# ESP32.net
KiCad netlist of a schematic drawn in Altium Designer
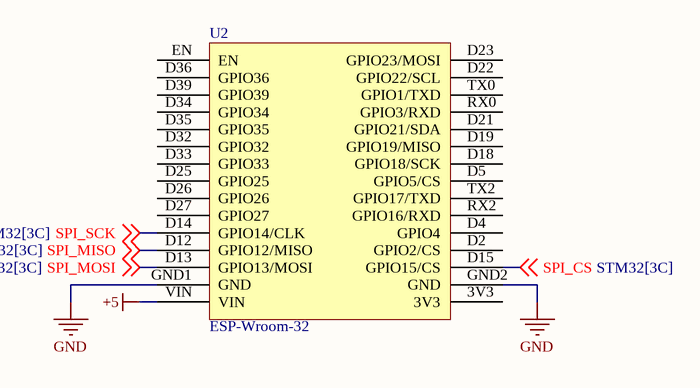
[diagram p0: ESP32.SchDoc]

(export (version "E")
  (design (tool "Eeschema 10.0.6"))
  (components
    (comp (ref "U2")
      (value "ESP-Wroom-32")
      (footprint "MODULE_ESP32_DEVKIT_V1")
      (description "https://lastminuteengineers.com/esp32-pinout-reference/")
      (libsource (lib "MindControlledCarPCB") (part "ESP-Wroom-32"))
    )
  )
  (nets
    (net (code "1") (name "+5") (class "Default")
      (node (ref "U2") (pin "VIN") (pinfunction "VIN_VIN") (pintype "passive"))
    )
    (net (code "2") (name "GND") (class "Default")
      (node (ref "U2") (pin "GND1") (pinfunction "GND_GND1") (pintype "passive"))
      (node (ref "U2") (pin "GND2") (pinfunction "GND_GND2") (pintype "passive"))
    )
    (net (code "3") (name "SPI_CS") (class "Default")
      (node (ref "U2") (pin "D15") (pinfunction "GPIO15/CS_D15") (pintype "passive"))
    )
    (net (code "4") (name "SPI_MISO") (class "Default")
      (node (ref "U2") (pin "D12") (pinfunction "GPIO12/MISO_D12") (pintype "passive"))
    )
    (net (code "5") (name "SPI_MOSI") (class "Default")
      (node (ref "U2") (pin "D13") (pinfunction "GPIO13/MOSI_D13") (pintype "passive"))
    )
    (net (code "6") (name "SPI_SCK") (class "Default")
      (node (ref "U2") (pin "D14") (pinfunction "GPIO14/CLK_D14") (pintype "passive"))
    )
    (net (code "7") (name "unconnected-(U2-GPIO1{slash}TXD-PadTX0)") (class "Default")
      (node (ref "U2") (pin "TX0") (pinfunction "GPIO1/TXD_TX0") (pintype "passive"))
    )
    (net (code "8") (name "unconnected-(U2-GPIO2{slash}CS-PadD2)") (class "Default")
      (node (ref "U2") (pin "D2") (pinfunction "GPIO2/CS_D2") (pintype "passive"))
    )
    (net (code "9") (name "unconnected-(U2-GPIO3{slash}RXD-PadRX0)") (class "Default")
      (node (ref "U2") (pin "RX0") (pinfunction "GPIO3/RXD_RX0") (pintype "passive"))
    )
    (net (code "10") (name "unconnected-(U2-GPIO4-PadD4)") (class "Default")
      (node (ref "U2") (pin "D4") (pinfunction "GPIO4_D4") (pintype "passive"))
    )
    (net (code "11") (name "unconnected-(U2-GPIO5{slash}CS-PadD5)") (class "Default")
      (node (ref "U2") (pin "D5") (pinfunction "GPIO5/CS_D5") (pintype "passive"))
    )
    (net (code "12") (name "unconnected-(U2-GPIO16{slash}RXD-PadRX2)") (class "Default")
      (node (ref "U2") (pin "RX2") (pinfunction "GPIO16/RXD_RX2") (pintype "passive"))
    )
    (net (code "13") (name "unconnected-(U2-GPIO17{slash}TXD-PadTX2)") (class "Default")
      (node (ref "U2") (pin "TX2") (pinfunction "GPIO17/TXD_TX2") (pintype "passive"))
    )
    (net (code "14") (name "unconnected-(U2-GPIO18{slash}SCK-PadD18)") (class "Default")
      (node (ref "U2") (pin "D18") (pinfunction "GPIO18/SCK_D18") (pintype "passive"))
    )
    (net (code "15") (name "unconnected-(U2-GPIO19{slash}MISO-PadD19)") (class "Default")
      (node (ref "U2") (pin "D19") (pinfunction "GPIO19/MISO_D19") (pintype "passive"))
    )
    (net (code "16") (name "unconnected-(U2-GPIO21{slash}SDA-PadD21)") (class "Default")
      (node (ref "U2") (pin "D21") (pinfunction "GPIO21/SDA_D21") (pintype "passive"))
    )
    (net (code "17") (name "unconnected-(U2-GPIO22{slash}SCL-PadD22)") (class "Default")
      (node (ref "U2") (pin "D22") (pinfunction "GPIO22/SCL_D22") (pintype "passive"))
    )
    (net (code "18") (name "unconnected-(U2-GPIO23{slash}MOSI-PadD23)") (class "Default")
      (node (ref "U2") (pin "D23") (pinfunction "GPIO23/MOSI_D23") (pintype "passive"))
    )
    (net (code "19") (name "unconnected-(U2-GPIO25-PadD25)") (class "Default")
      (node (ref "U2") (pin "D25") (pinfunction "GPIO25_D25") (pintype "passive"))
    )
    (net (code "20") (name "unconnected-(U2-GPIO26-PadD26)") (class "Default")
      (node (ref "U2") (pin "D26") (pinfunction "GPIO26_D26") (pintype "passive"))
    )
    (net (code "21") (name "unconnected-(U2-GPIO27-PadD27)") (class "Default")
      (node (ref "U2") (pin "D27") (pinfunction "GPIO27_D27") (pintype "passive"))
    )
    (net (code "22") (name "unconnected-(U2-GPIO32-PadD32)") (class "Default")
      (node (ref "U2") (pin "D32") (pinfunction "GPIO32_D32") (pintype "passive"))
    )
    (net (code "23") (name "unconnected-(U2-GPIO33-PadD33)") (class "Default")
      (node (ref "U2") (pin "D33") (pinfunction "GPIO33_D33") (pintype "passive"))
    )
    (net (code "24") (name "unconnected-(U2-GPIO34-PadD34)") (class "Default")
      (node (ref "U2") (pin "D34") (pinfunction "GPIO34_D34") (pintype "passive"))
    )
    (net (code "25") (name "unconnected-(U2-GPIO35-PadD35)") (class "Default")
      (node (ref "U2") (pin "D35") (pinfunction "GPIO35_D35") (pintype "passive"))
    )
    (net (code "26") (name "unconnected-(U2-GPIO36-PadD36)") (class "Default")
      (node (ref "U2") (pin "D36") (pinfunction "GPIO36_D36") (pintype "passive"))
    )
    (net (code "27") (name "unconnected-(U2-GPIO39-PadD39)") (class "Default")
      (node (ref "U2") (pin "D39") (pinfunction "GPIO39_D39") (pintype "passive"))
    )
    (net (code "28") (name "unconnected-(U2-Pad3V3)") (class "Default")
      (node (ref "U2") (pin "3V3") (pinfunction "3V3_3V3") (pintype "passive"))
    )
    (net (code "29") (name "unconnected-(U2-PadEN)") (class "Default")
      (node (ref "U2") (pin "EN") (pinfunction "EN_EN") (pintype "passive"))
    )
  )
)
